# S02.net
KiCad netlist of a schematic drawn in Altium Designer
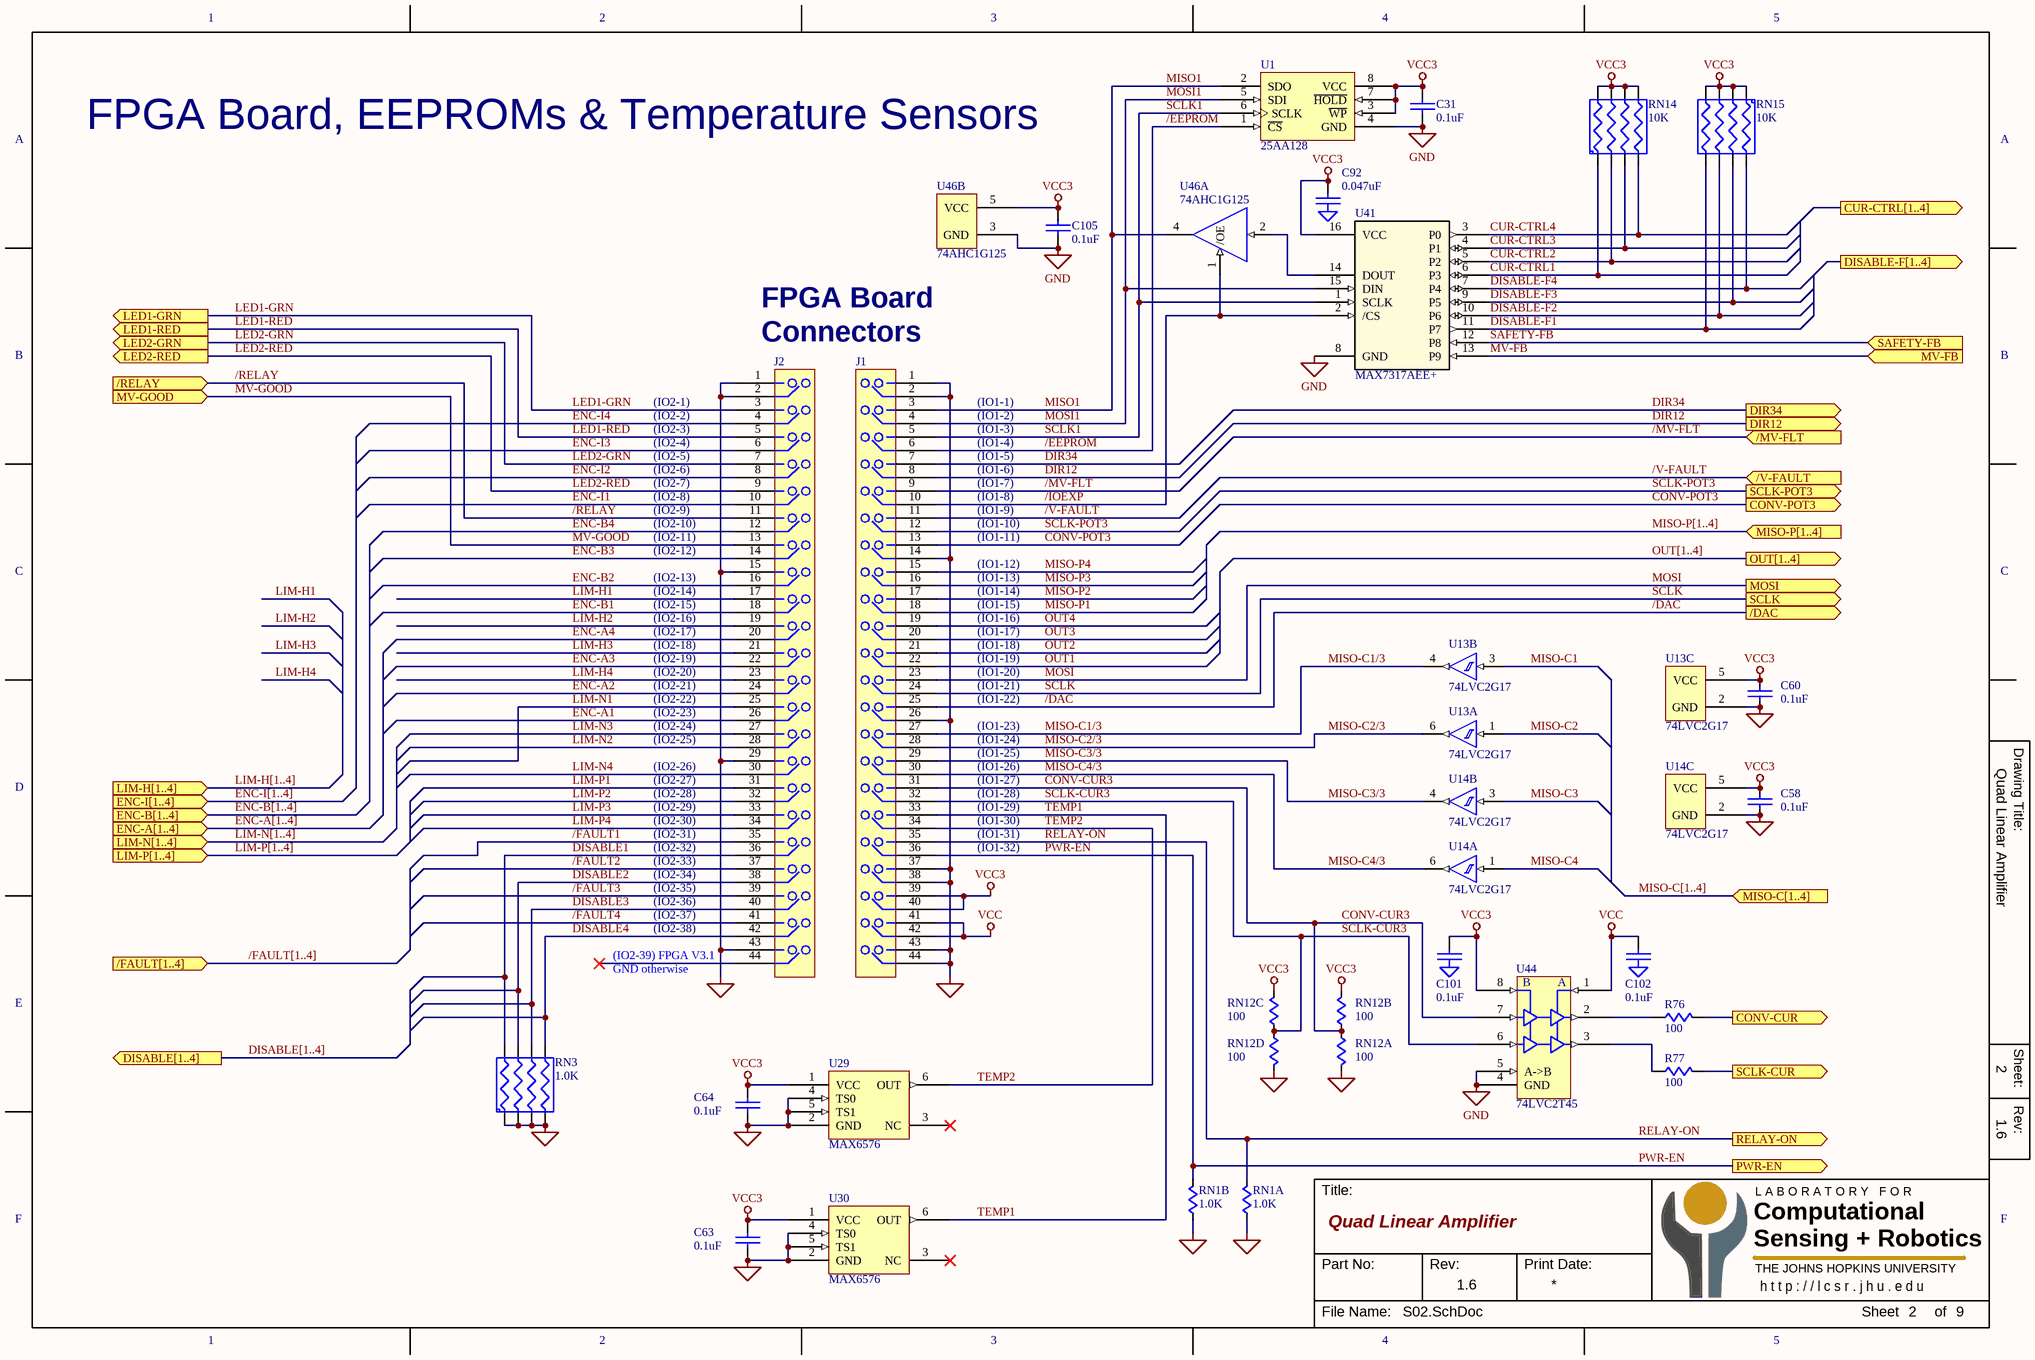
[diagram p0: S02.SchDoc]

(export (version "E")
  (design (tool "Eeschema 10.0.6"))
  (components
    (comp (ref "C31") (value "0.1uF") (footprint "C0603") (libsource (lib "QLA") (part "CAP")))
    (comp (ref "C58") (value "0.1uF") (footprint "C0603") (libsource (lib "QLA") (part "CAP-MINI")))
    (comp (ref "C60") (value "0.1uF") (footprint "C0603") (libsource (lib "QLA") (part "CAP-MINI")))
    (comp (ref "C63") (value "0.1uF") (footprint "C0603") (libsource (lib "QLA") (part "CAP")))
    (comp (ref "C64") (value "0.1uF") (footprint "C0603") (libsource (lib "QLA") (part "CAP")))
    (comp (ref "C92") (value "0.047uF") (footprint "C0603") (libsource (lib "QLA") (part "CAP-GND")))
    (comp (ref "C101") (value "0.1uF") (footprint "C0603") (libsource (lib "QLA") (part "CAP-GND")))
    (comp (ref "C102") (value "0.1uF") (footprint "C0603") (libsource (lib "QLA") (part "CAP-GND")))
    (comp (ref "C105") (value "0.1uF") (footprint "C0603") (libsource (lib "QLA") (part "CAP")))
    (comp (ref "J1")
      (value "HEADER 22x2-1")
      (footprint "HDR-22x2-2MM")
      (libsource (lib "QLA") (part "HEADER 22x2-1"))
    )
    (comp (ref "J2")
      (value "HEADER 22x2-1")
      (footprint "HDR-22x2-2MM")
      (libsource (lib "QLA") (part "HEADER 22x2-1"))
    )
    (comp (ref "R76") (value "100") (footprint "R0603") (libsource (lib "QLA") (part "R")))
    (comp (ref "R77") (value "100") (footprint "R0603") (libsource (lib "QLA") (part "R")))
    (comp (ref "RN1") (value "1.0K") (footprint "RN-742C083") (libsource (lib "QLA") (part "RN-DISC-SM-4X")))
    (comp (ref "RN3") (value "1.0K") (footprint "RN-742C083") (libsource (lib "QLA") (part "RN-DISC-SM-4")))
    (comp (ref "RN12") (value "100") (footprint "RN-742C083") (libsource (lib "QLA") (part "RN-DISC-SM-4X")))
    (comp (ref "RN14") (value "10K") (footprint "RN-742C083") (libsource (lib "QLA") (part "RN-DISC-SM-4")))
    (comp (ref "RN15") (value "10K") (footprint "RN-742C083") (libsource (lib "QLA") (part "RN-DISC-SM-4")))
    (comp (ref "U1") (value "25AA128") (footprint "TSSOP-8") (libsource (lib "QLA") (part "25AA128")))
    (comp (ref "U13")
      (value "74LVC2G17")
      (footprint "SOT-23-6")
      (description "NC7WZ17")
      (libsource (lib "QLA") (part "2G17"))
    )
    (comp (ref "U14")
      (value "74LVC2G17")
      (footprint "SOT-23-6")
      (description "NC7WZ17")
      (libsource (lib "QLA") (part "2G17"))
    )
    (comp (ref "U29") (value "MAX6576") (footprint "SOT-23-6") (libsource (lib "QLA") (part "MAX6576")))
    (comp (ref "U30") (value "MAX6576") (footprint "SOT-23-6") (libsource (lib "QLA") (part "MAX6576")))
    (comp (ref "U41")
      (value "MAX7317AEE+")
      (footprint "QSOP-16")
      (fields (field (name "COPYRIGHT") "Copyright (C) 2021 Accelerated Designs. All rights reserved"))
      (libsource (lib "QLA") (part "MAX7317AEE+"))
    )
    (comp (ref "U44") (value "74LVC2T45") (footprint "US8-8") (libsource (lib "QLA") (part "74LVC2T45")))
    (comp (ref "U46") (value "74AHC1G125") (footprint "SOT-23-5") (libsource (lib "") (part "74AHC1G125_1")))
  )
  (nets
    (net (code "5") (name "/CONV-CUR") (class "Default")
      (node (ref "R76") (pin "2") (pinfunction "2_2") (pintype "passive"))
    )
    (net (code "6") (name "/CONV-CUR3") (class "Default")
      (node (ref "J1") (pin "31") (pinfunction "31_31") (pintype "passive"))
      (node (ref "RN12") (pin "1") (pinfunction "1_1") (pintype "passive"))
      (node (ref "RN12") (pin "2") (pinfunction "2_2") (pintype "passive"))
      (node (ref "U44") (pin "7") (pinfunction "B_7") (pintype "input"))
    )
    (net (code "7") (name "/CONV-POT3") (class "Default")
      (node (ref "J1") (pin "13") (pinfunction "13_13") (pintype "passive"))
    )
    (net (code "8") (name "/CUR-CTRL1") (class "Default")
      (node (ref "RN14") (pin "1") (pinfunction "R1_1") (pintype "passive"))
      (node (ref "U41") (pin "6") (pinfunction "P3_6") (pintype "bidirectional"))
    )
    (net (code "9") (name "/CUR-CTRL2") (class "Default")
      (node (ref "RN14") (pin "2") (pinfunction "R2.1_2") (pintype "passive"))
      (node (ref "U41") (pin "5") (pinfunction "P2_5") (pintype "bidirectional"))
    )
    (net (code "10") (name "/CUR-CTRL3") (class "Default")
      (node (ref "RN14") (pin "3") (pinfunction "R3.1_3") (pintype "passive"))
      (node (ref "U41") (pin "4") (pinfunction "P1_4") (pintype "bidirectional"))
    )
    (net (code "11") (name "/CUR-CTRL4") (class "Default")
      (node (ref "RN14") (pin "4") (pinfunction "R4.1_4") (pintype "passive"))
      (node (ref "U41") (pin "3") (pinfunction "P0_3") (pintype "output"))
    )
    (net (code "13") (name "/DIR12") (class "Default")
      (node (ref "J1") (pin "8") (pinfunction "8_8") (pintype "passive"))
    )
    (net (code "14") (name "/DIR34") (class "Default")
      (node (ref "J1") (pin "7") (pinfunction "7_7") (pintype "passive"))
    )
    (net (code "15") (name "/DISABLE-F1") (class "Default")
      (node (ref "RN15") (pin "5") (pinfunction "R4.2_5") (pintype "passive"))
      (node (ref "U41") (pin "11") (pinfunction "P7_11") (pintype "output"))
    )
    (net (code "16") (name "/DISABLE-F2") (class "Default")
      (node (ref "RN15") (pin "6") (pinfunction "R3.2_6") (pintype "passive"))
      (node (ref "U41") (pin "10") (pinfunction "P6_10") (pintype "bidirectional"))
    )
    (net (code "17") (name "/DISABLE-F3") (class "Default")
      (node (ref "RN15") (pin "7") (pinfunction "R2.2_7") (pintype "passive"))
      (node (ref "U41") (pin "9") (pinfunction "P5_9") (pintype "bidirectional"))
    )
    (net (code "18") (name "/DISABLE-F4") (class "Default")
      (node (ref "RN15") (pin "8") (pinfunction "R1.2_8") (pintype "passive"))
      (node (ref "U41") (pin "7") (pinfunction "P4_7") (pintype "bidirectional"))
    )
    (net (code "20") (name "/DISABLE1") (class "Default")
      (node (ref "J2") (pin "36") (pinfunction "36_36") (pintype "passive"))
      (node (ref "RN3") (pin "8") (pinfunction "R1.2_8") (pintype "passive"))
    )
    (net (code "21") (name "/DISABLE2") (class "Default")
      (node (ref "J2") (pin "38") (pinfunction "38_38") (pintype "passive"))
      (node (ref "RN3") (pin "7") (pinfunction "R2.2_7") (pintype "passive"))
    )
    (net (code "22") (name "/DISABLE3") (class "Default")
      (node (ref "J2") (pin "40") (pinfunction "40_40") (pintype "passive"))
      (node (ref "RN3") (pin "6") (pinfunction "R3.2_6") (pintype "passive"))
    )
    (net (code "23") (name "/DISABLE4") (class "Default")
      (node (ref "J2") (pin "42") (pinfunction "42_42") (pintype "passive"))
      (node (ref "RN3") (pin "5") (pinfunction "R4.2_5") (pintype "passive"))
    )
    (net (code "25") (name "/ENC-A1") (class "Default")
      (node (ref "J2") (pin "26") (pinfunction "26_26") (pintype "passive"))
    )
    (net (code "26") (name "/ENC-A2") (class "Default")
      (node (ref "J2") (pin "24") (pinfunction "24_24") (pintype "passive"))
    )
    (net (code "27") (name "/ENC-A3") (class "Default")
      (node (ref "J2") (pin "22") (pinfunction "22_22") (pintype "passive"))
    )
    (net (code "28") (name "/ENC-A4") (class "Default")
      (node (ref "J2") (pin "20") (pinfunction "20_20") (pintype "passive"))
    )
    (net (code "30") (name "/ENC-B1") (class "Default")
      (node (ref "J2") (pin "18") (pinfunction "18_18") (pintype "passive"))
    )
    (net (code "31") (name "/ENC-B2") (class "Default")
      (node (ref "J2") (pin "16") (pinfunction "16_16") (pintype "passive"))
    )
    (net (code "32") (name "/ENC-B3") (class "Default")
      (node (ref "J2") (pin "14") (pinfunction "14_14") (pintype "passive"))
    )
    (net (code "33") (name "/ENC-B4") (class "Default")
      (node (ref "J2") (pin "12") (pinfunction "12_12") (pintype "passive"))
    )
    (net (code "35") (name "/ENC-I1") (class "Default")
      (node (ref "J2") (pin "10") (pinfunction "10_10") (pintype "passive"))
    )
    (net (code "36") (name "/ENC-I2") (class "Default")
      (node (ref "J2") (pin "8") (pinfunction "8_8") (pintype "passive"))
    )
    (net (code "37") (name "/ENC-I3") (class "Default")
      (node (ref "J2") (pin "6") (pinfunction "6_6") (pintype "passive"))
    )
    (net (code "38") (name "/ENC-I4") (class "Default")
      (node (ref "J2") (pin "4") (pinfunction "4_4") (pintype "passive"))
    )
    (net (code "40") (name "/LED1-GRN") (class "Default")
      (node (ref "J2") (pin "3") (pinfunction "3_3") (pintype "passive"))
    )
    (net (code "41") (name "/LED1-RED") (class "Default")
      (node (ref "J2") (pin "5") (pinfunction "5_5") (pintype "passive"))
    )
    (net (code "42") (name "/LED2-GRN") (class "Default")
      (node (ref "J2") (pin "7") (pinfunction "7_7") (pintype "passive"))
    )
    (net (code "43") (name "/LED2-RED") (class "Default")
      (node (ref "J2") (pin "9") (pinfunction "9_9") (pintype "passive"))
    )
    (net (code "44") (name "/LIM-H1") (class "Default")
      (node (ref "J2") (pin "17") (pinfunction "17_17") (pintype "passive"))
    )
    (net (code "45") (name "/LIM-H2") (class "Default")
      (node (ref "J2") (pin "19") (pinfunction "19_19") (pintype "passive"))
    )
    (net (code "46") (name "/LIM-H3") (class "Default")
      (node (ref "J2") (pin "21") (pinfunction "21_21") (pintype "passive"))
    )
    (net (code "47") (name "/LIM-H4") (class "Default")
      (node (ref "J2") (pin "23") (pinfunction "23_23") (pintype "passive"))
    )
    (net (code "49") (name "/LIM-N1") (class "Default")
      (node (ref "J2") (pin "25") (pinfunction "25_25") (pintype "passive"))
    )
    (net (code "50") (name "/LIM-N2") (class "Default")
      (node (ref "J2") (pin "28") (pinfunction "28_28") (pintype "passive"))
    )
    (net (code "51") (name "/LIM-N3") (class "Default")
      (node (ref "J2") (pin "27") (pinfunction "27_27") (pintype "passive"))
    )
    (net (code "52") (name "/LIM-N4") (class "Default")
      (node (ref "J2") (pin "30") (pinfunction "30_30") (pintype "passive"))
    )
    (net (code "54") (name "/LIM-P1") (class "Default")
      (node (ref "J2") (pin "31") (pinfunction "31_31") (pintype "passive"))
    )
    (net (code "55") (name "/LIM-P2") (class "Default")
      (node (ref "J2") (pin "32") (pinfunction "32_32") (pintype "passive"))
    )
    (net (code "56") (name "/LIM-P3") (class "Default")
      (node (ref "J2") (pin "33") (pinfunction "33_33") (pintype "passive"))
    )
    (net (code "57") (name "/LIM-P4") (class "Default")
      (node (ref "J2") (pin "34") (pinfunction "34_34") (pintype "passive"))
    )
    (net (code "59") (name "/MISO-C1") (class "Default") (node (ref "U13") (pin "3") (pintype "input")))
    (net (code "60") (name "/MISO-C1{slash}3") (class "Default")
      (node (ref "J1") (pin "27") (pinfunction "27_27") (pintype "passive"))
      (node (ref "U13") (pin "4") (pintype "output"))
    )
    (net (code "61") (name "/MISO-C2") (class "Default") (node (ref "U13") (pin "1") (pintype "input")))
    (net (code "62") (name "/MISO-C2{slash}3") (class "Default")
      (node (ref "J1") (pin "28") (pinfunction "28_28") (pintype "passive"))
      (node (ref "U13") (pin "6") (pintype "output"))
    )
    (net (code "63") (name "/MISO-C3") (class "Default") (node (ref "U14") (pin "3") (pintype "input")))
    (net (code "64") (name "/MISO-C3{slash}3") (class "Default")
      (node (ref "J1") (pin "29") (pinfunction "29_29") (pintype "passive"))
      (node (ref "U14") (pin "4") (pintype "output"))
    )
    (net (code "65") (name "/MISO-C4") (class "Default") (node (ref "U14") (pin "1") (pintype "input")))
    (net (code "66") (name "/MISO-C4{slash}3") (class "Default")
      (node (ref "J1") (pin "30") (pinfunction "30_30") (pintype "passive"))
      (node (ref "U14") (pin "6") (pintype "output"))
    )
    (net (code "68") (name "/MISO-P1") (class "Default")
      (node (ref "J1") (pin "18") (pinfunction "18_18") (pintype "passive"))
    )
    (net (code "69") (name "/MISO-P2") (class "Default")
      (node (ref "J1") (pin "17") (pinfunction "17_17") (pintype "passive"))
    )
    (net (code "70") (name "/MISO-P3") (class "Default")
      (node (ref "J1") (pin "16") (pinfunction "16_16") (pintype "passive"))
    )
    (net (code "71") (name "/MISO-P4") (class "Default")
      (node (ref "J1") (pin "15") (pinfunction "15_15") (pintype "passive"))
    )
    (net (code "73") (name "/MISO1") (class "Default")
      (node (ref "J1") (pin "3") (pinfunction "3_3") (pintype "passive"))
      (node (ref "U1") (pin "2") (pinfunction "SDO_2") (pintype "tri_state"))
      (node (ref "U46") (pin "4") (pinfunction "Y_4") (pintype "tri_state"))
    )
    (net (code "74") (name "/MOSI") (class "Default")
      (node (ref "J1") (pin "23") (pinfunction "23_23") (pintype "passive"))
    )
    (net (code "75") (name "/MOSI1") (class "Default")
      (node (ref "J1") (pin "4") (pinfunction "4_4") (pintype "passive"))
      (node (ref "U1") (pin "5") (pinfunction "SDI_5") (pintype "input"))
      (node (ref "U41") (pin "15") (pinfunction "DIN_15") (pintype "input"))
    )
    (net (code "76") (name "/MV-FB") (class "Default")
      (node (ref "U41") (pin "13") (pinfunction "P9_13") (pintype "input"))
    )
    (net (code "77") (name "/MV-GOOD") (class "Default")
      (node (ref "J2") (pin "13") (pinfunction "13_13") (pintype "passive"))
    )
    (net (code "78") (name "/OUT1") (class "Default")
      (node (ref "J1") (pin "22") (pinfunction "22_22") (pintype "passive"))
    )
    (net (code "79") (name "/OUT2") (class "Default")
      (node (ref "J1") (pin "21") (pinfunction "21_21") (pintype "passive"))
    )
    (net (code "80") (name "/OUT3") (class "Default")
      (node (ref "J1") (pin "20") (pinfunction "20_20") (pintype "passive"))
    )
    (net (code "81") (name "/OUT4") (class "Default")
      (node (ref "J1") (pin "19") (pinfunction "19_19") (pintype "passive"))
    )
    (net (code "83") (name "/PWR-EN") (class "Default")
      (node (ref "J1") (pin "36") (pinfunction "36_36") (pintype "passive"))
      (node (ref "RN1") (pin "7") (pinfunction "7_7") (pintype "passive"))
    )
    (net (code "84") (name "/RELAY-ON") (class "Default")
      (node (ref "J1") (pin "35") (pinfunction "35_35") (pintype "passive"))
      (node (ref "RN1") (pin "8") (pinfunction "8_8") (pintype "passive"))
    )
    (net (code "85") (name "/SAFETY-FB") (class "Default")
      (node (ref "U41") (pin "12") (pinfunction "P8_12") (pintype "input"))
    )
    (net (code "86") (name "/SCLK") (class "Default")
      (node (ref "J1") (pin "24") (pinfunction "24_24") (pintype "passive"))
    )
    (net (code "87") (name "/SCLK-CUR") (class "Default")
      (node (ref "R77") (pin "2") (pinfunction "2_2") (pintype "passive"))
    )
    (net (code "88") (name "/SCLK-CUR3") (class "Default")
      (node (ref "J1") (pin "32") (pinfunction "32_32") (pintype "passive"))
      (node (ref "RN12") (pin "3") (pinfunction "3_3") (pintype "passive"))
      (node (ref "RN12") (pin "4") (pinfunction "4_4") (pintype "passive"))
      (node (ref "U44") (pin "6") (pinfunction "B_6") (pintype "input"))
    )
    (net (code "89") (name "/SCLK-POT3") (class "Default")
      (node (ref "J1") (pin "12") (pinfunction "12_12") (pintype "passive"))
    )
    (net (code "90") (name "/SCLK1") (class "Default")
      (node (ref "J1") (pin "5") (pinfunction "5_5") (pintype "passive"))
      (node (ref "U1") (pin "6") (pinfunction "SCLK_6") (pintype "input"))
      (node (ref "U41") (pin "1") (pinfunction "SCLK_1") (pintype "input"))
    )
    (net (code "91") (name "/TEMP1") (class "Default")
      (node (ref "J1") (pin "33") (pinfunction "33_33") (pintype "passive"))
      (node (ref "U30") (pin "6") (pinfunction "OUT_6") (pintype "output"))
    )
    (net (code "92") (name "/TEMP2") (class "Default")
      (node (ref "J1") (pin "34") (pinfunction "34_34") (pintype "passive"))
      (node (ref "U29") (pin "6") (pinfunction "OUT_6") (pintype "output"))
    )
    (net (code "93") (name "/{slash}DAC") (class "Default")
      (node (ref "J1") (pin "25") (pinfunction "25_25") (pintype "passive"))
    )
    (net (code "94") (name "/{slash}EEPROM") (class "Default")
      (node (ref "J1") (pin "6") (pinfunction "6_6") (pintype "passive"))
      (node (ref "U1") (pin "1") (pinfunction "CS_1") (pintype "input"))
    )
    (net (code "95") (name "/{slash}FAULT1") (class "Default")
      (node (ref "J2") (pin "35") (pinfunction "35_35") (pintype "passive"))
    )
    (net (code "96") (name "/{slash}FAULT2") (class "Default")
      (node (ref "J2") (pin "37") (pinfunction "37_37") (pintype "passive"))
    )
    (net (code "97") (name "/{slash}FAULT3") (class "Default")
      (node (ref "J2") (pin "39") (pinfunction "39_39") (pintype "passive"))
    )
    (net (code "98") (name "/{slash}FAULT4") (class "Default")
      (node (ref "J2") (pin "41") (pinfunction "41_41") (pintype "passive"))
    )
    (net (code "100") (name "/{slash}IOEXP") (class "Default")
      (node (ref "J1") (pin "10") (pinfunction "10_10") (pintype "passive"))
      (node (ref "U41") (pin "2") (pinfunction "/CS_2") (pintype "input"))
      (node (ref "U46") (pin "1") (pinfunction "/OE_1") (pintype "input"))
    )
    (net (code "101") (name "/{slash}MV-FLT") (class "Default")
      (node (ref "J1") (pin "9") (pinfunction "9_9") (pintype "passive"))
    )
    (net (code "102") (name "/{slash}RELAY") (class "Default")
      (node (ref "J2") (pin "11") (pinfunction "11_11") (pintype "passive"))
    )
    (net (code "103") (name "/{slash}V-FAULT") (class "Default")
      (node (ref "J1") (pin "11") (pinfunction "11_11") (pintype "passive"))
    )
    (net (code "104") (name "GND") (class "Default")
      (node (ref "C101") (pin "2") (pinfunction "GND_2") (pintype "power_in"))
      (node (ref "C102") (pin "2") (pinfunction "GND_2") (pintype "power_in"))
      (node (ref "C105") (pin "2") (pintype "passive"))
      (node (ref "C31") (pin "2") (pintype "passive"))
      (node (ref "C58") (pin "2") (pintype "passive"))
      (node (ref "C60") (pin "2") (pintype "passive"))
      (node (ref "C63") (pin "2") (pintype "passive"))
      (node (ref "C64") (pin "2") (pintype "passive"))
      (node (ref "C92") (pin "2") (pinfunction "GND_2") (pintype "power_in"))
      (node (ref "J1") (pin "1") (pinfunction "1_1") (pintype "passive"))
      (node (ref "J1") (pin "14") (pinfunction "14_14") (pintype "passive"))
      (node (ref "J1") (pin "2") (pinfunction "2_2") (pintype "passive"))
      (node (ref "J1") (pin "26") (pinfunction "26_26") (pintype "passive"))
      (node (ref "J1") (pin "37") (pinfunction "37_37") (pintype "passive"))
      (node (ref "J1") (pin "38") (pinfunction "38_38") (pintype "passive"))
      (node (ref "J1") (pin "43") (pinfunction "43_43") (pintype "passive"))
      (node (ref "J1") (pin "44") (pinfunction "44_44") (pintype "passive"))
      (node (ref "J2") (pin "1") (pinfunction "1_1") (pintype "passive"))
      (node (ref "J2") (pin "15") (pinfunction "15_15") (pintype "passive"))
      (node (ref "J2") (pin "2") (pinfunction "2_2") (pintype "passive"))
      (node (ref "J2") (pin "29") (pinfunction "29_29") (pintype "passive"))
      (node (ref "J2") (pin "43") (pinfunction "43_43") (pintype "passive"))
      (node (ref "RN1") (pin "1") (pinfunction "1_1") (pintype "passive"))
      (node (ref "RN1") (pin "2") (pinfunction "2_2") (pintype "passive"))
      (node (ref "RN12") (pin "5") (pinfunction "5_5") (pintype "passive"))
      (node (ref "RN12") (pin "8") (pinfunction "8_8") (pintype "passive"))
      (node (ref "RN3") (pin "1") (pinfunction "R1_1") (pintype "passive"))
      (node (ref "RN3") (pin "2") (pinfunction "R2.1_2") (pintype "passive"))
      (node (ref "RN3") (pin "3") (pinfunction "R3.1_3") (pintype "passive"))
      (node (ref "RN3") (pin "4") (pinfunction "R4.1_4") (pintype "passive"))
      (node (ref "U1") (pin "4") (pinfunction "GND_4") (pintype "power_in"))
      (node (ref "U13") (pin "2") (pinfunction "GND_2") (pintype "power_in"))
      (node (ref "U14") (pin "2") (pinfunction "GND_2") (pintype "power_in"))
      (node (ref "U29") (pin "2") (pinfunction "GND_2") (pintype "power_in"))
      (node (ref "U29") (pin "4") (pinfunction "TS0_4") (pintype "input"))
      (node (ref "U29") (pin "5") (pinfunction "TS1_5") (pintype "input"))
      (node (ref "U30") (pin "2") (pinfunction "GND_2") (pintype "power_in"))
      (node (ref "U30") (pin "4") (pinfunction "TS0_4") (pintype "input"))
      (node (ref "U30") (pin "5") (pinfunction "TS1_5") (pintype "input"))
      (node (ref "U41") (pin "8") (pinfunction "GND_8") (pintype "power_in"))
      (node (ref "U44") (pin "4") (pinfunction "GND_4") (pintype "power_in"))
      (node (ref "U44") (pin "5") (pinfunction "A->B_5") (pintype "input"))
      (node (ref "U46") (pin "3") (pinfunction "GND_3") (pintype "power_in"))
    )
    (net (code "105") (name "Net-(R76-Pad1)") (class "Default")
      (node (ref "R76") (pin "1") (pinfunction "1_1") (pintype "passive"))
      (node (ref "U44") (pin "2") (pinfunction "A_2") (pintype "output"))
    )
    (net (code "106") (name "Net-(R77-Pad1)") (class "Default")
      (node (ref "R77") (pin "1") (pinfunction "1_1") (pintype "passive"))
      (node (ref "U44") (pin "3") (pinfunction "A_3") (pintype "output"))
    )
    (net (code "107") (name "Net-(U41-DOUT)") (class "Default")
      (node (ref "U41") (pin "14") (pinfunction "DOUT_14") (pintype "tri_state"))
      (node (ref "U46") (pin "2") (pinfunction "A_2") (pintype "input"))
    )
    (net (code "108") (name "VCC") (class "Default")
      (node (ref "C102") (pin "1") (pintype "passive"))
      (node (ref "J1") (pin "41") (pinfunction "41_41") (pintype "passive"))
      (node (ref "J1") (pin "42") (pinfunction "42_42") (pintype "passive"))
      (node (ref "U44") (pin "1") (pinfunction "VCCA_1") (pintype "input"))
    )
    (net (code "109") (name "VCC3") (class "Default")
      (node (ref "C101") (pin "1") (pintype "passive"))
      (node (ref "C105") (pin "1") (pintype "passive"))
      (node (ref "C31") (pin "1") (pintype "passive"))
      (node (ref "C58") (pin "1") (pintype "passive"))
      (node (ref "C60") (pin "1") (pintype "passive"))
      (node (ref "C63") (pin "1") (pintype "passive"))
      (node (ref "C64") (pin "1") (pintype "passive"))
      (node (ref "C92") (pin "1") (pintype "passive"))
      (node (ref "J1") (pin "39") (pinfunction "39_39") (pintype "passive"))
      (node (ref "J1") (pin "40") (pinfunction "40_40") (pintype "passive"))
      (node (ref "RN12") (pin "6") (pinfunction "6_6") (pintype "passive"))
      (node (ref "RN12") (pin "7") (pinfunction "7_7") (pintype "passive"))
      (node (ref "RN14") (pin "5") (pinfunction "R4.2_5") (pintype "passive"))
      (node (ref "RN14") (pin "6") (pinfunction "R3.2_6") (pintype "passive"))
      (node (ref "RN14") (pin "7") (pinfunction "R2.2_7") (pintype "passive"))
      (node (ref "RN14") (pin "8") (pinfunction "R1.2_8") (pintype "passive"))
      (node (ref "RN15") (pin "1") (pinfunction "R1_1") (pintype "passive"))
      (node (ref "RN15") (pin "2") (pinfunction "R2.1_2") (pintype "passive"))
      (node (ref "RN15") (pin "3") (pinfunction "R3.1_3") (pintype "passive"))
      (node (ref "RN15") (pin "4") (pinfunction "R4.1_4") (pintype "passive"))
      (node (ref "U1") (pin "3") (pinfunction "WP_3") (pintype "input"))
      (node (ref "U1") (pin "7") (pinfunction "HOLD_7") (pintype "input"))
      (node (ref "U1") (pin "8") (pinfunction "VCC_8") (pintype "power_in"))
      (node (ref "U13") (pin "5") (pinfunction "VCC_5") (pintype "power_in"))
      (node (ref "U14") (pin "5") (pinfunction "VCC_5") (pintype "power_in"))
      (node (ref "U29") (pin "1") (pinfunction "VCC_1") (pintype "power_in"))
      (node (ref "U30") (pin "1") (pinfunction "VCC_1") (pintype "power_in"))
      (node (ref "U41") (pin "16") (pinfunction "VCC_16") (pintype "power_in"))
      (node (ref "U44") (pin "8") (pinfunction "VCCB_8") (pintype "input"))
      (node (ref "U46") (pin "5") (pinfunction "VCC_5") (pintype "power_in"))
    )
    (net (code "110") (name "unconnected-(J2-Pad44)") (class "Default")
      (node (ref "J2") (pin "44") (pinfunction "44_44") (pintype "passive+no_connect"))
    )
    (net (code "111") (name "unconnected-(U29-NC-Pad3)") (class "Default")
      (node (ref "U29") (pin "3") (pinfunction "NC_3") (pintype "passive+no_connect"))
    )
    (net (code "112") (name "unconnected-(U30-NC-Pad3)") (class "Default")
      (node (ref "U30") (pin "3") (pinfunction "NC_3") (pintype "passive+no_connect"))
    )
  )
)
